# ADC-DMUX_PSU.net
KiCad netlist of a schematic drawn in Altium Designer
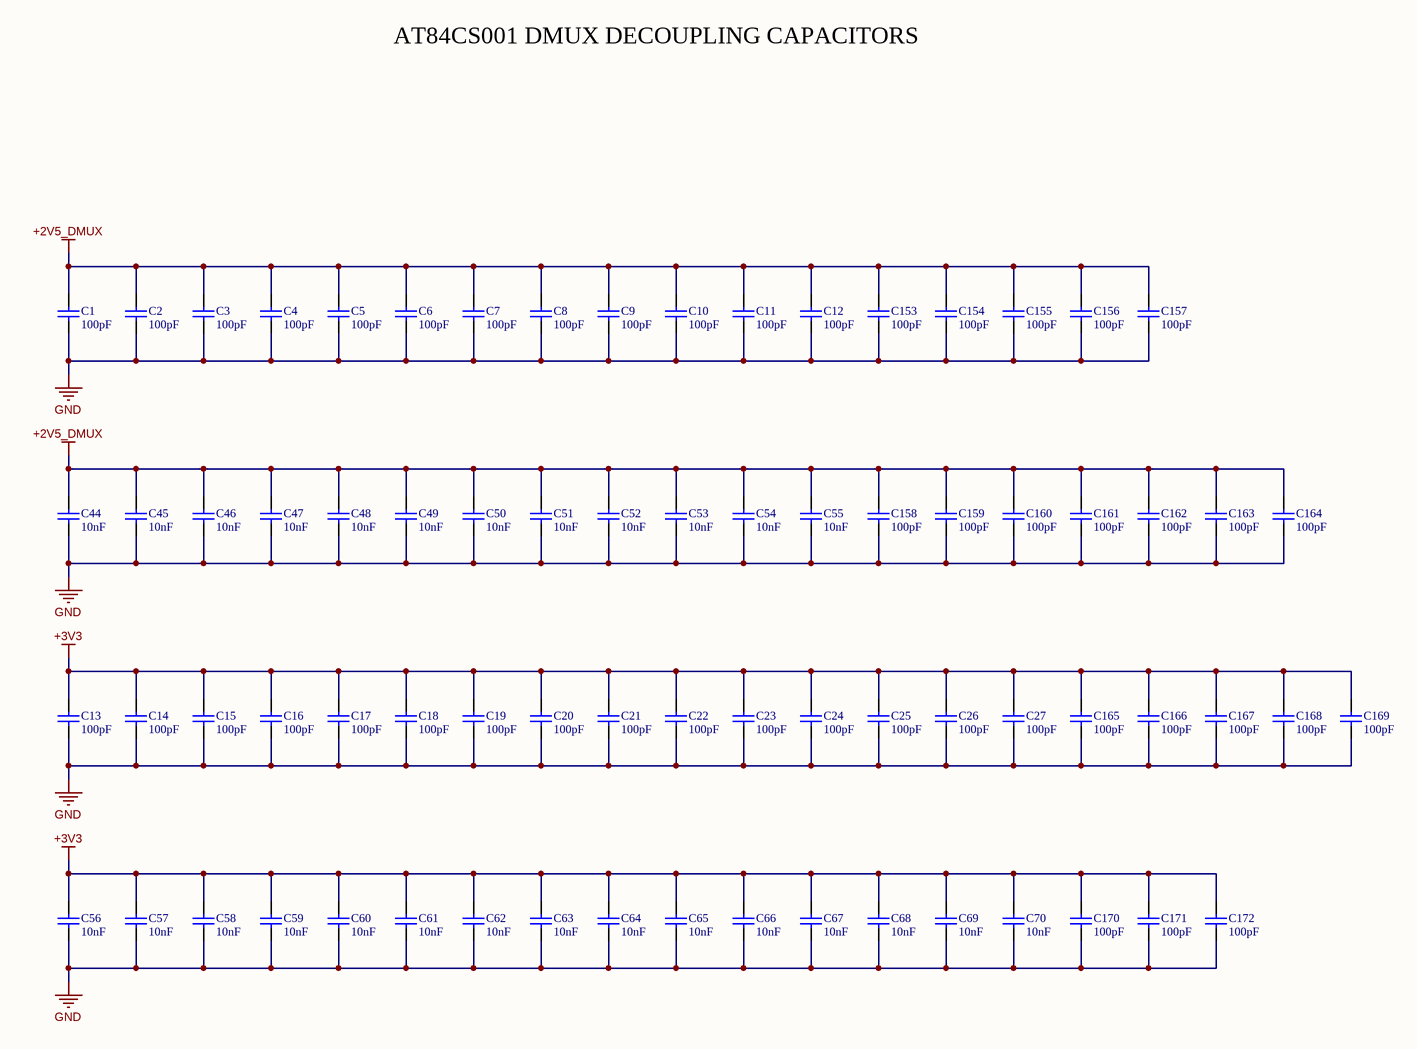
[diagram p0: ADC-DMUX PSU.SchDoc]

(export (version "E")
  (design (tool "Eeschema 10.0.6"))
  (components
    (comp (ref "C1")
      (value "100pF")
      (footprint "CAPC1005X55N")
      (description "Capacitor 0402 SMD")
      (fields (field (name "CREATED_BY") "EDA-ASA") (field (name "CHECKED_BY") "*"))
      (libsource (lib "EDA-Passive") (part "cap0402"))
    )
    (comp (ref "C2")
      (value "100pF")
      (footprint "CAPC1005X55N")
      (description "Capacitor 0402 SMD")
      (fields (field (name "CREATED_BY") "EDA-ASA") (field (name "CHECKED_BY") "*"))
      (libsource (lib "EDA-Passive") (part "cap0402"))
    )
    (comp (ref "C3")
      (value "100pF")
      (footprint "CAPC1005X55N")
      (description "Capacitor 0402 SMD")
      (fields (field (name "CREATED_BY") "EDA-ASA") (field (name "CHECKED_BY") "*"))
      (libsource (lib "EDA-Passive") (part "cap0402"))
    )
    (comp (ref "C4")
      (value "100pF")
      (footprint "CAPC1005X55N")
      (description "Capacitor 0402 SMD")
      (fields (field (name "CREATED_BY") "EDA-ASA") (field (name "CHECKED_BY") "*"))
      (libsource (lib "EDA-Passive") (part "cap0402"))
    )
    (comp (ref "C5")
      (value "100pF")
      (footprint "CAPC1005X55N")
      (description "Capacitor 0402 SMD")
      (fields (field (name "CREATED_BY") "EDA-ASA") (field (name "CHECKED_BY") "*"))
      (libsource (lib "EDA-Passive") (part "cap0402"))
    )
    (comp (ref "C6")
      (value "100pF")
      (footprint "CAPC1005X55N")
      (description "Capacitor 0402 SMD")
      (fields (field (name "CREATED_BY") "EDA-ASA") (field (name "CHECKED_BY") "*"))
      (libsource (lib "EDA-Passive") (part "cap0402"))
    )
    (comp (ref "C7")
      (value "100pF")
      (footprint "CAPC1005X55N")
      (description "Capacitor 0402 SMD")
      (fields (field (name "CREATED_BY") "EDA-ASA") (field (name "CHECKED_BY") "*"))
      (libsource (lib "EDA-Passive") (part "cap0402"))
    )
    (comp (ref "C8")
      (value "100pF")
      (footprint "CAPC1005X55N")
      (description "Capacitor 0402 SMD")
      (fields (field (name "CREATED_BY") "EDA-ASA") (field (name "CHECKED_BY") "*"))
      (libsource (lib "EDA-Passive") (part "cap0402"))
    )
    (comp (ref "C9")
      (value "100pF")
      (footprint "CAPC1005X55N")
      (description "Capacitor 0402 SMD")
      (fields (field (name "CREATED_BY") "EDA-ASA") (field (name "CHECKED_BY") "*"))
      (libsource (lib "EDA-Passive") (part "cap0402"))
    )
    (comp (ref "C10")
      (value "100pF")
      (footprint "CAPC1005X55N")
      (description "Capacitor 0402 SMD")
      (fields (field (name "CREATED_BY") "EDA-ASA") (field (name "CHECKED_BY") "*"))
      (libsource (lib "EDA-Passive") (part "cap0402"))
    )
    (comp (ref "C11")
      (value "100pF")
      (footprint "CAPC1005X55N")
      (description "Capacitor 0402 SMD")
      (fields (field (name "CREATED_BY") "EDA-ASA") (field (name "CHECKED_BY") "*"))
      (libsource (lib "EDA-Passive") (part "cap0402"))
    )
    (comp (ref "C12")
      (value "100pF")
      (footprint "CAPC1005X55N")
      (description "Capacitor 0402 SMD")
      (fields (field (name "CREATED_BY") "EDA-ASA") (field (name "CHECKED_BY") "*"))
      (libsource (lib "EDA-Passive") (part "cap0402"))
    )
    (comp (ref "C13")
      (value "100pF")
      (footprint "CAPC1005X55N")
      (description "Capacitor 0402 SMD")
      (fields (field (name "CREATED_BY") "EDA-ASA") (field (name "CHECKED_BY") "*"))
      (libsource (lib "EDA-Passive") (part "cap0402"))
    )
    (comp (ref "C14")
      (value "100pF")
      (footprint "CAPC1005X55N")
      (description "Capacitor 0402 SMD")
      (fields (field (name "CREATED_BY") "EDA-ASA") (field (name "CHECKED_BY") "*"))
      (libsource (lib "EDA-Passive") (part "cap0402"))
    )
    (comp (ref "C15")
      (value "100pF")
      (footprint "CAPC1005X55N")
      (description "Capacitor 0402 SMD")
      (fields (field (name "CREATED_BY") "EDA-ASA") (field (name "CHECKED_BY") "*"))
      (libsource (lib "EDA-Passive") (part "cap0402"))
    )
    (comp (ref "C16")
      (value "100pF")
      (footprint "CAPC1005X55N")
      (description "Capacitor 0402 SMD")
      (fields (field (name "CREATED_BY") "EDA-ASA") (field (name "CHECKED_BY") "*"))
      (libsource (lib "EDA-Passive") (part "cap0402"))
    )
    (comp (ref "C17")
      (value "100pF")
      (footprint "CAPC1005X55N")
      (description "Capacitor 0402 SMD")
      (fields (field (name "CREATED_BY") "EDA-ASA") (field (name "CHECKED_BY") "*"))
      (libsource (lib "EDA-Passive") (part "cap0402"))
    )
    (comp (ref "C18")
      (value "100pF")
      (footprint "CAPC1005X55N")
      (description "Capacitor 0402 SMD")
      (fields (field (name "CREATED_BY") "EDA-ASA") (field (name "CHECKED_BY") "*"))
      (libsource (lib "EDA-Passive") (part "cap0402"))
    )
    (comp (ref "C19")
      (value "100pF")
      (footprint "CAPC1005X55N")
      (description "Capacitor 0402 SMD")
      (fields (field (name "CREATED_BY") "EDA-ASA") (field (name "CHECKED_BY") "*"))
      (libsource (lib "EDA-Passive") (part "cap0402"))
    )
    (comp (ref "C20")
      (value "100pF")
      (footprint "CAPC1005X55N")
      (description "Capacitor 0402 SMD")
      (fields (field (name "CREATED_BY") "EDA-ASA") (field (name "CHECKED_BY") "*"))
      (libsource (lib "EDA-Passive") (part "cap0402"))
    )
    (comp (ref "C21")
      (value "100pF")
      (footprint "CAPC1005X55N")
      (description "Capacitor 0402 SMD")
      (fields (field (name "CREATED_BY") "EDA-ASA") (field (name "CHECKED_BY") "*"))
      (libsource (lib "EDA-Passive") (part "cap0402"))
    )
    (comp (ref "C22")
      (value "100pF")
      (footprint "CAPC1005X55N")
      (description "Capacitor 0402 SMD")
      (fields (field (name "CREATED_BY") "EDA-ASA") (field (name "CHECKED_BY") "*"))
      (libsource (lib "EDA-Passive") (part "cap0402"))
    )
    (comp (ref "C23")
      (value "100pF")
      (footprint "CAPC1005X55N")
      (description "Capacitor 0402 SMD")
      (fields (field (name "CREATED_BY") "EDA-ASA") (field (name "CHECKED_BY") "*"))
      (libsource (lib "EDA-Passive") (part "cap0402"))
    )
    (comp (ref "C24")
      (value "100pF")
      (footprint "CAPC1005X55N")
      (description "Capacitor 0402 SMD")
      (fields (field (name "CREATED_BY") "EDA-ASA") (field (name "CHECKED_BY") "*"))
      (libsource (lib "EDA-Passive") (part "cap0402"))
    )
    (comp (ref "C25")
      (value "100pF")
      (footprint "CAPC1005X55N")
      (description "Capacitor 0402 SMD")
      (fields (field (name "CREATED_BY") "EDA-ASA") (field (name "CHECKED_BY") "*"))
      (libsource (lib "EDA-Passive") (part "cap0402"))
    )
    (comp (ref "C26")
      (value "100pF")
      (footprint "CAPC1005X55N")
      (description "Capacitor 0402 SMD")
      (fields (field (name "CREATED_BY") "EDA-ASA") (field (name "CHECKED_BY") "*"))
      (libsource (lib "EDA-Passive") (part "cap0402"))
    )
    (comp (ref "C27")
      (value "100pF")
      (footprint "CAPC1005X55N")
      (description "Capacitor 0402 SMD")
      (fields (field (name "CREATED_BY") "EDA-ASA") (field (name "CHECKED_BY") "*"))
      (libsource (lib "EDA-Passive") (part "cap0402"))
    )
    (comp (ref "C44")
      (value "10nF")
      (footprint "CAPC1005X55N")
      (description "Capacitor 0402 SMD")
      (fields (field (name "CREATED_BY") "EDA-ASA") (field (name "CHECKED_BY") "*"))
      (libsource (lib "EDA-Passive") (part "cap0402"))
    )
    (comp (ref "C45")
      (value "10nF")
      (footprint "CAPC1005X55N")
      (description "Capacitor 0402 SMD")
      (fields (field (name "CREATED_BY") "EDA-ASA") (field (name "CHECKED_BY") "*"))
      (libsource (lib "EDA-Passive") (part "cap0402"))
    )
    (comp (ref "C46")
      (value "10nF")
      (footprint "CAPC1005X55N")
      (description "Capacitor 0402 SMD")
      (fields (field (name "CREATED_BY") "EDA-ASA") (field (name "CHECKED_BY") "*"))
      (libsource (lib "EDA-Passive") (part "cap0402"))
    )
    (comp (ref "C47")
      (value "10nF")
      (footprint "CAPC1005X55N")
      (description "Capacitor 0402 SMD")
      (fields (field (name "CREATED_BY") "EDA-ASA") (field (name "CHECKED_BY") "*"))
      (libsource (lib "EDA-Passive") (part "cap0402"))
    )
    (comp (ref "C48")
      (value "10nF")
      (footprint "CAPC1005X55N")
      (description "Capacitor 0402 SMD")
      (fields (field (name "CREATED_BY") "EDA-ASA") (field (name "CHECKED_BY") "*"))
      (libsource (lib "EDA-Passive") (part "cap0402"))
    )
    (comp (ref "C49")
      (value "10nF")
      (footprint "CAPC1005X55N")
      (description "Capacitor 0402 SMD")
      (fields (field (name "CREATED_BY") "EDA-ASA") (field (name "CHECKED_BY") "*"))
      (libsource (lib "EDA-Passive") (part "cap0402"))
    )
    (comp (ref "C50")
      (value "10nF")
      (footprint "CAPC1005X55N")
      (description "Capacitor 0402 SMD")
      (fields (field (name "CREATED_BY") "EDA-ASA") (field (name "CHECKED_BY") "*"))
      (libsource (lib "EDA-Passive") (part "cap0402"))
    )
    (comp (ref "C51")
      (value "10nF")
      (footprint "CAPC1005X55N")
      (description "Capacitor 0402 SMD")
      (fields (field (name "CREATED_BY") "EDA-ASA") (field (name "CHECKED_BY") "*"))
      (libsource (lib "EDA-Passive") (part "cap0402"))
    )
    (comp (ref "C52")
      (value "10nF")
      (footprint "CAPC1005X55N")
      (description "Capacitor 0402 SMD")
      (fields (field (name "CREATED_BY") "EDA-ASA") (field (name "CHECKED_BY") "*"))
      (libsource (lib "EDA-Passive") (part "cap0402"))
    )
    (comp (ref "C53")
      (value "10nF")
      (footprint "CAPC1005X55N")
      (description "Capacitor 0402 SMD")
      (fields (field (name "CREATED_BY") "EDA-ASA") (field (name "CHECKED_BY") "*"))
      (libsource (lib "EDA-Passive") (part "cap0402"))
    )
    (comp (ref "C54")
      (value "10nF")
      (footprint "CAPC1005X55N")
      (description "Capacitor 0402 SMD")
      (fields (field (name "CREATED_BY") "EDA-ASA") (field (name "CHECKED_BY") "*"))
      (libsource (lib "EDA-Passive") (part "cap0402"))
    )
    (comp (ref "C55")
      (value "10nF")
      (footprint "CAPC1005X55N")
      (description "Capacitor 0402 SMD")
      (fields (field (name "CREATED_BY") "EDA-ASA") (field (name "CHECKED_BY") "*"))
      (libsource (lib "EDA-Passive") (part "cap0402"))
    )
    (comp (ref "C56")
      (value "10nF")
      (footprint "CAPC1005X55N")
      (description "Capacitor 0402 SMD")
      (fields (field (name "CREATED_BY") "EDA-ASA") (field (name "CHECKED_BY") "*"))
      (libsource (lib "EDA-Passive") (part "cap0402"))
    )
    (comp (ref "C57")
      (value "10nF")
      (footprint "CAPC1005X55N")
      (description "Capacitor 0402 SMD")
      (fields (field (name "CREATED_BY") "EDA-ASA") (field (name "CHECKED_BY") "*"))
      (libsource (lib "EDA-Passive") (part "cap0402"))
    )
    (comp (ref "C58")
      (value "10nF")
      (footprint "CAPC1005X55N")
      (description "Capacitor 0402 SMD")
      (fields (field (name "CREATED_BY") "EDA-ASA") (field (name "CHECKED_BY") "*"))
      (libsource (lib "EDA-Passive") (part "cap0402"))
    )
    (comp (ref "C59")
      (value "10nF")
      (footprint "CAPC1005X55N")
      (description "Capacitor 0402 SMD")
      (fields (field (name "CREATED_BY") "EDA-ASA") (field (name "CHECKED_BY") "*"))
      (libsource (lib "EDA-Passive") (part "cap0402"))
    )
    (comp (ref "C60")
      (value "10nF")
      (footprint "CAPC1005X55N")
      (description "Capacitor 0402 SMD")
      (fields (field (name "CREATED_BY") "EDA-ASA") (field (name "CHECKED_BY") "*"))
      (libsource (lib "EDA-Passive") (part "cap0402"))
    )
    (comp (ref "C61")
      (value "10nF")
      (footprint "CAPC1005X55N")
      (description "Capacitor 0402 SMD")
      (fields (field (name "CREATED_BY") "EDA-ASA") (field (name "CHECKED_BY") "*"))
      (libsource (lib "EDA-Passive") (part "cap0402"))
    )
    (comp (ref "C62")
      (value "10nF")
      (footprint "CAPC1005X55N")
      (description "Capacitor 0402 SMD")
      (fields (field (name "CREATED_BY") "EDA-ASA") (field (name "CHECKED_BY") "*"))
      (libsource (lib "EDA-Passive") (part "cap0402"))
    )
    (comp (ref "C63")
      (value "10nF")
      (footprint "CAPC1005X55N")
      (description "Capacitor 0402 SMD")
      (fields (field (name "CREATED_BY") "EDA-ASA") (field (name "CHECKED_BY") "*"))
      (libsource (lib "EDA-Passive") (part "cap0402"))
    )
    (comp (ref "C64")
      (value "10nF")
      (footprint "CAPC1005X55N")
      (description "Capacitor 0402 SMD")
      (fields (field (name "CREATED_BY") "EDA-ASA") (field (name "CHECKED_BY") "*"))
      (libsource (lib "EDA-Passive") (part "cap0402"))
    )
    (comp (ref "C65")
      (value "10nF")
      (footprint "CAPC1005X55N")
      (description "Capacitor 0402 SMD")
      (fields (field (name "CREATED_BY") "EDA-ASA") (field (name "CHECKED_BY") "*"))
      (libsource (lib "EDA-Passive") (part "cap0402"))
    )
    (comp (ref "C66")
      (value "10nF")
      (footprint "CAPC1005X55N")
      (description "Capacitor 0402 SMD")
      (fields (field (name "CREATED_BY") "EDA-ASA") (field (name "CHECKED_BY") "*"))
      (libsource (lib "EDA-Passive") (part "cap0402"))
    )
    (comp (ref "C67")
      (value "10nF")
      (footprint "CAPC1005X55N")
      (description "Capacitor 0402 SMD")
      (fields (field (name "CREATED_BY") "EDA-ASA") (field (name "CHECKED_BY") "*"))
      (libsource (lib "EDA-Passive") (part "cap0402"))
    )
    (comp (ref "C68")
      (value "10nF")
      (footprint "CAPC1005X55N")
      (description "Capacitor 0402 SMD")
      (fields (field (name "CREATED_BY") "EDA-ASA") (field (name "CHECKED_BY") "*"))
      (libsource (lib "EDA-Passive") (part "cap0402"))
    )
    (comp (ref "C69")
      (value "10nF")
      (footprint "CAPC1005X55N")
      (description "Capacitor 0402 SMD")
      (fields (field (name "CREATED_BY") "EDA-ASA") (field (name "CHECKED_BY") "*"))
      (libsource (lib "EDA-Passive") (part "cap0402"))
    )
    (comp (ref "C70")
      (value "10nF")
      (footprint "CAPC1005X55N")
      (description "Capacitor 0402 SMD")
      (fields (field (name "CREATED_BY") "EDA-ASA") (field (name "CHECKED_BY") "*"))
      (libsource (lib "EDA-Passive") (part "cap0402"))
    )
    (comp (ref "C153")
      (value "100pF")
      (footprint "CAPC1005X55N")
      (description "Capacitor 0402 SMD")
      (fields (field (name "CREATED_BY") "EDA-ASA") (field (name "CHECKED_BY") "*"))
      (libsource (lib "EDA-Passive") (part "cap0402"))
    )
    (comp (ref "C154")
      (value "100pF")
      (footprint "CAPC1005X55N")
      (description "Capacitor 0402 SMD")
      (fields (field (name "CREATED_BY") "EDA-ASA") (field (name "CHECKED_BY") "*"))
      (libsource (lib "EDA-Passive") (part "cap0402"))
    )
    (comp (ref "C155")
      (value "100pF")
      (footprint "CAPC1005X55N")
      (description "Capacitor 0402 SMD")
      (fields (field (name "CREATED_BY") "EDA-ASA") (field (name "CHECKED_BY") "*"))
      (libsource (lib "EDA-Passive") (part "cap0402"))
    )
    (comp (ref "C156")
      (value "100pF")
      (footprint "CAPC1005X55N")
      (description "Capacitor 0402 SMD")
      (fields (field (name "CREATED_BY") "EDA-ASA") (field (name "CHECKED_BY") "*"))
      (libsource (lib "EDA-Passive") (part "cap0402"))
    )
    (comp (ref "C157")
      (value "100pF")
      (footprint "CAPC1005X55N")
      (description "Capacitor 0402 SMD")
      (fields (field (name "CREATED_BY") "EDA-ASA") (field (name "CHECKED_BY") "*"))
      (libsource (lib "EDA-Passive") (part "cap0402"))
    )
    (comp (ref "C158")
      (value "100pF")
      (footprint "CAPC1005X55N")
      (description "Capacitor 0402 SMD")
      (fields (field (name "CREATED_BY") "EDA-ASA") (field (name "CHECKED_BY") "*"))
      (libsource (lib "EDA-Passive") (part "cap0402"))
    )
    (comp (ref "C159")
      (value "100pF")
      (footprint "CAPC1005X55N")
      (description "Capacitor 0402 SMD")
      (fields (field (name "CREATED_BY") "EDA-ASA") (field (name "CHECKED_BY") "*"))
      (libsource (lib "EDA-Passive") (part "cap0402"))
    )
    (comp (ref "C160")
      (value "100pF")
      (footprint "CAPC1005X55N")
      (description "Capacitor 0402 SMD")
      (fields (field (name "CREATED_BY") "EDA-ASA") (field (name "CHECKED_BY") "*"))
      (libsource (lib "EDA-Passive") (part "cap0402"))
    )
    (comp (ref "C161")
      (value "100pF")
      (footprint "CAPC1005X55N")
      (description "Capacitor 0402 SMD")
      (fields (field (name "CREATED_BY") "EDA-ASA") (field (name "CHECKED_BY") "*"))
      (libsource (lib "EDA-Passive") (part "cap0402"))
    )
    (comp (ref "C162")
      (value "100pF")
      (footprint "CAPC1005X55N")
      (description "Capacitor 0402 SMD")
      (fields (field (name "CREATED_BY") "EDA-ASA") (field (name "CHECKED_BY") "*"))
      (libsource (lib "EDA-Passive") (part "cap0402"))
    )
    (comp (ref "C163")
      (value "100pF")
      (footprint "CAPC1005X55N")
      (description "Capacitor 0402 SMD")
      (fields (field (name "CREATED_BY") "EDA-ASA") (field (name "CHECKED_BY") "*"))
      (libsource (lib "EDA-Passive") (part "cap0402"))
    )
    (comp (ref "C164")
      (value "100pF")
      (footprint "CAPC1005X55N")
      (description "Capacitor 0402 SMD")
      (fields (field (name "CREATED_BY") "EDA-ASA") (field (name "CHECKED_BY") "*"))
      (libsource (lib "EDA-Passive") (part "cap0402"))
    )
    (comp (ref "C165")
      (value "100pF")
      (footprint "CAPC1005X55N")
      (description "Capacitor 0402 SMD")
      (fields (field (name "CREATED_BY") "EDA-ASA") (field (name "CHECKED_BY") "*"))
      (libsource (lib "EDA-Passive") (part "cap0402"))
    )
    (comp (ref "C166")
      (value "100pF")
      (footprint "CAPC1005X55N")
      (description "Capacitor 0402 SMD")
      (fields (field (name "CREATED_BY") "EDA-ASA") (field (name "CHECKED_BY") "*"))
      (libsource (lib "EDA-Passive") (part "cap0402"))
    )
    (comp (ref "C167")
      (value "100pF")
      (footprint "CAPC1005X55N")
      (description "Capacitor 0402 SMD")
      (fields (field (name "CREATED_BY") "EDA-ASA") (field (name "CHECKED_BY") "*"))
      (libsource (lib "EDA-Passive") (part "cap0402"))
    )
    (comp (ref "C168")
      (value "100pF")
      (footprint "CAPC1005X55N")
      (description "Capacitor 0402 SMD")
      (fields (field (name "CREATED_BY") "EDA-ASA") (field (name "CHECKED_BY") "*"))
      (libsource (lib "EDA-Passive") (part "cap0402"))
    )
    (comp (ref "C169")
      (value "100pF")
      (footprint "CAPC1005X55N")
      (description "Capacitor 0402 SMD")
      (fields (field (name "CREATED_BY") "EDA-ASA") (field (name "CHECKED_BY") "*"))
      (libsource (lib "EDA-Passive") (part "cap0402"))
    )
    (comp (ref "C170")
      (value "100pF")
      (footprint "CAPC1005X55N")
      (description "Capacitor 0402 SMD")
      (fields (field (name "CREATED_BY") "EDA-ASA") (field (name "CHECKED_BY") "*"))
      (libsource (lib "EDA-Passive") (part "cap0402"))
    )
    (comp (ref "C171")
      (value "100pF")
      (footprint "CAPC1005X55N")
      (description "Capacitor 0402 SMD")
      (fields (field (name "CREATED_BY") "EDA-ASA") (field (name "CHECKED_BY") "*"))
      (libsource (lib "EDA-Passive") (part "cap0402"))
    )
    (comp (ref "C172")
      (value "100pF")
      (footprint "CAPC1005X55N")
      (description "Capacitor 0402 SMD")
      (fields (field (name "CREATED_BY") "EDA-ASA") (field (name "CHECKED_BY") "*"))
      (libsource (lib "EDA-Passive") (part "cap0402"))
    )
  )
  (nets
    (net (code "1") (name "+2V5_DMUX") (class "Default")
      (node (ref "C1") (pin "1") (pinfunction "1_1") (pintype "passive"))
      (node (ref "C10") (pin "1") (pinfunction "1_1") (pintype "passive"))
      (node (ref "C11") (pin "1") (pinfunction "1_1") (pintype "passive"))
      (node (ref "C12") (pin "1") (pinfunction "1_1") (pintype "passive"))
      (node (ref "C153") (pin "1") (pinfunction "1_1") (pintype "passive"))
      (node (ref "C154") (pin "1") (pinfunction "1_1") (pintype "passive"))
      (node (ref "C155") (pin "1") (pinfunction "1_1") (pintype "passive"))
      (node (ref "C156") (pin "1") (pinfunction "1_1") (pintype "passive"))
      (node (ref "C157") (pin "1") (pinfunction "1_1") (pintype "passive"))
      (node (ref "C158") (pin "1") (pinfunction "1_1") (pintype "passive"))
      (node (ref "C159") (pin "1") (pinfunction "1_1") (pintype "passive"))
      (node (ref "C160") (pin "1") (pinfunction "1_1") (pintype "passive"))
      (node (ref "C161") (pin "1") (pinfunction "1_1") (pintype "passive"))
      (node (ref "C162") (pin "1") (pinfunction "1_1") (pintype "passive"))
      (node (ref "C163") (pin "1") (pinfunction "1_1") (pintype "passive"))
      (node (ref "C164") (pin "1") (pinfunction "1_1") (pintype "passive"))
      (node (ref "C2") (pin "1") (pinfunction "1_1") (pintype "passive"))
      (node (ref "C3") (pin "1") (pinfunction "1_1") (pintype "passive"))
      (node (ref "C4") (pin "1") (pinfunction "1_1") (pintype "passive"))
      (node (ref "C44") (pin "1") (pinfunction "1_1") (pintype "passive"))
      (node (ref "C45") (pin "1") (pinfunction "1_1") (pintype "passive"))
      (node (ref "C46") (pin "1") (pinfunction "1_1") (pintype "passive"))
      (node (ref "C47") (pin "1") (pinfunction "1_1") (pintype "passive"))
      (node (ref "C48") (pin "1") (pinfunction "1_1") (pintype "passive"))
      (node (ref "C49") (pin "1") (pinfunction "1_1") (pintype "passive"))
      (node (ref "C5") (pin "1") (pinfunction "1_1") (pintype "passive"))
      (node (ref "C50") (pin "1") (pinfunction "1_1") (pintype "passive"))
      (node (ref "C51") (pin "1") (pinfunction "1_1") (pintype "passive"))
      (node (ref "C52") (pin "1") (pinfunction "1_1") (pintype "passive"))
      (node (ref "C53") (pin "1") (pinfunction "1_1") (pintype "passive"))
      (node (ref "C54") (pin "1") (pinfunction "1_1") (pintype "passive"))
      (node (ref "C55") (pin "1") (pinfunction "1_1") (pintype "passive"))
      (node (ref "C6") (pin "1") (pinfunction "1_1") (pintype "passive"))
      (node (ref "C7") (pin "1") (pinfunction "1_1") (pintype "passive"))
      (node (ref "C8") (pin "1") (pinfunction "1_1") (pintype "passive"))
      (node (ref "C9") (pin "1") (pinfunction "1_1") (pintype "passive"))
    )
    (net (code "2") (name "+3V3") (class "Default")
      (node (ref "C13") (pin "1") (pinfunction "1_1") (pintype "passive"))
      (node (ref "C14") (pin "1") (pinfunction "1_1") (pintype "passive"))
      (node (ref "C15") (pin "1") (pinfunction "1_1") (pintype "passive"))
      (node (ref "C16") (pin "1") (pinfunction "1_1") (pintype "passive"))
      (node (ref "C165") (pin "1") (pinfunction "1_1") (pintype "passive"))
      (node (ref "C166") (pin "1") (pinfunction "1_1") (pintype "passive"))
      (node (ref "C167") (pin "1") (pinfunction "1_1") (pintype "passive"))
      (node (ref "C168") (pin "1") (pinfunction "1_1") (pintype "passive"))
      (node (ref "C169") (pin "1") (pinfunction "1_1") (pintype "passive"))
      (node (ref "C17") (pin "1") (pinfunction "1_1") (pintype "passive"))
      (node (ref "C170") (pin "1") (pinfunction "1_1") (pintype "passive"))
      (node (ref "C171") (pin "1") (pinfunction "1_1") (pintype "passive"))
      (node (ref "C172") (pin "1") (pinfunction "1_1") (pintype "passive"))
      (node (ref "C18") (pin "1") (pinfunction "1_1") (pintype "passive"))
      (node (ref "C19") (pin "1") (pinfunction "1_1") (pintype "passive"))
      (node (ref "C20") (pin "1") (pinfunction "1_1") (pintype "passive"))
      (node (ref "C21") (pin "1") (pinfunction "1_1") (pintype "passive"))
      (node (ref "C22") (pin "1") (pinfunction "1_1") (pintype "passive"))
      (node (ref "C23") (pin "1") (pinfunction "1_1") (pintype "passive"))
      (node (ref "C24") (pin "1") (pinfunction "1_1") (pintype "passive"))
      (node (ref "C25") (pin "1") (pinfunction "1_1") (pintype "passive"))
      (node (ref "C26") (pin "1") (pinfunction "1_1") (pintype "passive"))
      (node (ref "C27") (pin "1") (pinfunction "1_1") (pintype "passive"))
      (node (ref "C56") (pin "1") (pinfunction "1_1") (pintype "passive"))
      (node (ref "C57") (pin "1") (pinfunction "1_1") (pintype "passive"))
      (node (ref "C58") (pin "1") (pinfunction "1_1") (pintype "passive"))
      (node (ref "C59") (pin "1") (pinfunction "1_1") (pintype "passive"))
      (node (ref "C60") (pin "1") (pinfunction "1_1") (pintype "passive"))
      (node (ref "C61") (pin "1") (pinfunction "1_1") (pintype "passive"))
      (node (ref "C62") (pin "1") (pinfunction "1_1") (pintype "passive"))
      (node (ref "C63") (pin "1") (pinfunction "1_1") (pintype "passive"))
      (node (ref "C64") (pin "1") (pinfunction "1_1") (pintype "passive"))
      (node (ref "C65") (pin "1") (pinfunction "1_1") (pintype "passive"))
      (node (ref "C66") (pin "1") (pinfunction "1_1") (pintype "passive"))
      (node (ref "C67") (pin "1") (pinfunction "1_1") (pintype "passive"))
      (node (ref "C68") (pin "1") (pinfunction "1_1") (pintype "passive"))
      (node (ref "C69") (pin "1") (pinfunction "1_1") (pintype "passive"))
      (node (ref "C70") (pin "1") (pinfunction "1_1") (pintype "passive"))
    )
    (net (code "3") (name "GND") (class "Default")
      (node (ref "C1") (pin "2") (pinfunction "2_2") (pintype "passive"))
      (node (ref "C10") (pin "2") (pinfunction "2_2") (pintype "passive"))
      (node (ref "C11") (pin "2") (pinfunction "2_2") (pintype "passive"))
      (node (ref "C12") (pin "2") (pinfunction "2_2") (pintype "passive"))
      (node (ref "C13") (pin "2") (pinfunction "2_2") (pintype "passive"))
      (node (ref "C14") (pin "2") (pinfunction "2_2") (pintype "passive"))
      (node (ref "C15") (pin "2") (pinfunction "2_2") (pintype "passive"))
      (node (ref "C153") (pin "2") (pinfunction "2_2") (pintype "passive"))
      (node (ref "C154") (pin "2") (pinfunction "2_2") (pintype "passive"))
      (node (ref "C155") (pin "2") (pinfunction "2_2") (pintype "passive"))
      (node (ref "C156") (pin "2") (pinfunction "2_2") (pintype "passive"))
      (node (ref "C157") (pin "2") (pinfunction "2_2") (pintype "passive"))
      (node (ref "C158") (pin "2") (pinfunction "2_2") (pintype "passive"))
      (node (ref "C159") (pin "2") (pinfunction "2_2") (pintype "passive"))
      (node (ref "C16") (pin "2") (pinfunction "2_2") (pintype "passive"))
      (node (ref "C160") (pin "2") (pinfunction "2_2") (pintype "passive"))
      (node (ref "C161") (pin "2") (pinfunction "2_2") (pintype "passive"))
      (node (ref "C162") (pin "2") (pinfunction "2_2") (pintype "passive"))
      (node (ref "C163") (pin "2") (pinfunction "2_2") (pintype "passive"))
      (node (ref "C164") (pin "2") (pinfunction "2_2") (pintype "passive"))
      (node (ref "C165") (pin "2") (pinfunction "2_2") (pintype "passive"))
      (node (ref "C166") (pin "2") (pinfunction "2_2") (pintype "passive"))
      (node (ref "C167") (pin "2") (pinfunction "2_2") (pintype "passive"))
      (node (ref "C168") (pin "2") (pinfunction "2_2") (pintype "passive"))
      (node (ref "C169") (pin "2") (pinfunction "2_2") (pintype "passive"))
      (node (ref "C17") (pin "2") (pinfunction "2_2") (pintype "passive"))
      (node (ref "C170") (pin "2") (pinfunction "2_2") (pintype "passive"))
      (node (ref "C171") (pin "2") (pinfunction "2_2") (pintype "passive"))
      (node (ref "C172") (pin "2") (pinfunction "2_2") (pintype "passive"))
      (node (ref "C18") (pin "2") (pinfunction "2_2") (pintype "passive"))
      (node (ref "C19") (pin "2") (pinfunction "2_2") (pintype "passive"))
      (node (ref "C2") (pin "2") (pinfunction "2_2") (pintype "passive"))
      (node (ref "C20") (pin "2") (pinfunction "2_2") (pintype "passive"))
      (node (ref "C21") (pin "2") (pinfunction "2_2") (pintype "passive"))
      (node (ref "C22") (pin "2") (pinfunction "2_2") (pintype "passive"))
      (node (ref "C23") (pin "2") (pinfunction "2_2") (pintype "passive"))
      (node (ref "C24") (pin "2") (pinfunction "2_2") (pintype "passive"))
      (node (ref "C25") (pin "2") (pinfunction "2_2") (pintype "passive"))
      (node (ref "C26") (pin "2") (pinfunction "2_2") (pintype "passive"))
      (node (ref "C27") (pin "2") (pinfunction "2_2") (pintype "passive"))
      (node (ref "C3") (pin "2") (pinfunction "2_2") (pintype "passive"))
      (node (ref "C4") (pin "2") (pinfunction "2_2") (pintype "passive"))
      (node (ref "C44") (pin "2") (pinfunction "2_2") (pintype "passive"))
      (node (ref "C45") (pin "2") (pinfunction "2_2") (pintype "passive"))
      (node (ref "C46") (pin "2") (pinfunction "2_2") (pintype "passive"))
      (node (ref "C47") (pin "2") (pinfunction "2_2") (pintype "passive"))
      (node (ref "C48") (pin "2") (pinfunction "2_2") (pintype "passive"))
      (node (ref "C49") (pin "2") (pinfunction "2_2") (pintype "passive"))
      (node (ref "C5") (pin "2") (pinfunction "2_2") (pintype "passive"))
      (node (ref "C50") (pin "2") (pinfunction "2_2") (pintype "passive"))
      (node (ref "C51") (pin "2") (pinfunction "2_2") (pintype "passive"))
      (node (ref "C52") (pin "2") (pinfunction "2_2") (pintype "passive"))
      (node (ref "C53") (pin "2") (pinfunction "2_2") (pintype "passive"))
      (node (ref "C54") (pin "2") (pinfunction "2_2") (pintype "passive"))
      (node (ref "C55") (pin "2") (pinfunction "2_2") (pintype "passive"))
      (node (ref "C56") (pin "2") (pinfunction "2_2") (pintype "passive"))
      (node (ref "C57") (pin "2") (pinfunction "2_2") (pintype "passive"))
      (node (ref "C58") (pin "2") (pinfunction "2_2") (pintype "passive"))
      (node (ref "C59") (pin "2") (pinfunction "2_2") (pintype "passive"))
      (node (ref "C6") (pin "2") (pinfunction "2_2") (pintype "passive"))
      (node (ref "C60") (pin "2") (pinfunction "2_2") (pintype "passive"))
      (node (ref "C61") (pin "2") (pinfunction "2_2") (pintype "passive"))
      (node (ref "C62") (pin "2") (pinfunction "2_2") (pintype "passive"))
      (node (ref "C63") (pin "2") (pinfunction "2_2") (pintype "passive"))
      (node (ref "C64") (pin "2") (pinfunction "2_2") (pintype "passive"))
      (node (ref "C65") (pin "2") (pinfunction "2_2") (pintype "passive"))
      (node (ref "C66") (pin "2") (pinfunction "2_2") (pintype "passive"))
      (node (ref "C67") (pin "2") (pinfunction "2_2") (pintype "passive"))
      (node (ref "C68") (pin "2") (pinfunction "2_2") (pintype "passive"))
      (node (ref "C69") (pin "2") (pinfunction "2_2") (pintype "passive"))
      (node (ref "C7") (pin "2") (pinfunction "2_2") (pintype "passive"))
      (node (ref "C70") (pin "2") (pinfunction "2_2") (pintype "passive"))
      (node (ref "C8") (pin "2") (pinfunction "2_2") (pintype "passive"))
      (node (ref "C9") (pin "2") (pinfunction "2_2") (pintype "passive"))
    )
  )
)
